# 1_P1.net
KiCad netlist of a schematic drawn in Altium Designer
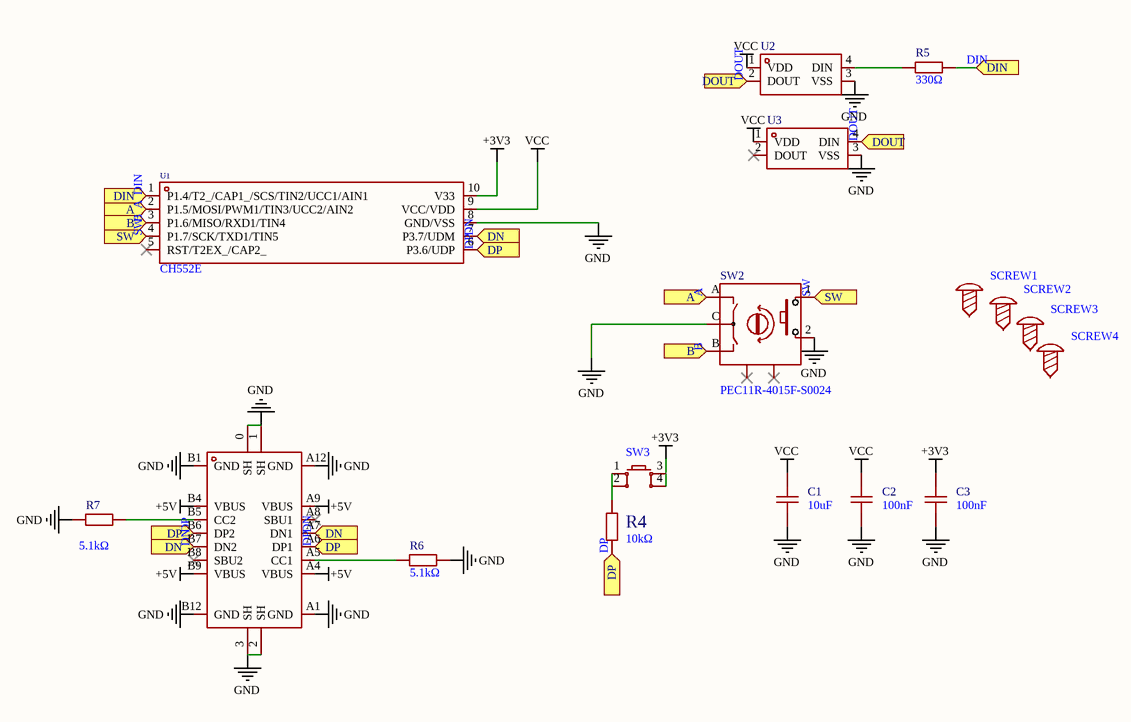
[diagram p0: 1_P1.schdoc]

(export (version "E")
  (design (tool "Eeschema 10.0.6"))
  (components
    (comp (ref "C1")
      (value "10uF")
      (footprint "C0603")
      (fields
        (field (name "MANUFACTURER") "SAMSUNG(三星)")
        (field (name "MANUFACTURER PART") "CL10A106KP8NNNC")
        (field (name "TOLERANCE") "±10%")
      )
      (libsource (lib "altium-import") (part "root_1_CL10A106KP8NNNC_"))
    )
    (comp (ref "C2")
      (value "100nF")
      (footprint "C0603")
      (fields
        (field (name "MANUFACTURER") "YAGEO(国巨)")
        (field (name "MANUFACTURER PART") "CC0603KRX7R9BB104")
        (field (name "TOLERANCE") "±10%")
      )
      (libsource (lib "altium-import") (part "root_1_CC0603KRX7R9BB104_"))
    )
    (comp (ref "C3")
      (value "100nF")
      (footprint "C0603")
      (fields
        (field (name "MANUFACTURER") "YAGEO(国巨)")
        (field (name "MANUFACTURER PART") "CC0603KRX7R9BB104")
        (field (name "TOLERANCE") "±10%")
      )
      (libsource (lib "altium-import") (part "root_1_CC0603KRX7R9BB104_"))
    )
    (comp (ref "R4")
      (value "10kΩ")
      (footprint "R0603")
      (fields
        (field (name "MANUFACTURER") "UNI-ROYAL(厚声)")
        (field (name "MANUFACTURER PART") "0603WAF1002T5E")
        (field (name "TOLERANCE") "±1%")
      )
      (libsource (lib "altium-import") (part "root_1_0603WAF1002T5E_"))
    )
    (comp (ref "R5")
      (value "330Ω")
      (footprint "R0603")
      (fields
        (field (name "MANUFACTURER") "UNI-ROYAL(厚声)")
        (field (name "MANUFACTURER PART") "0603WAF3300T5E")
        (field (name "TOLERANCE") "±1%")
      )
      (libsource (lib "altium-import") (part "root_0_0603WAF3300T5E_"))
    )
    (comp (ref "R6")
      (value "5.1kΩ")
      (footprint "R0603")
      (fields
        (field (name "MANUFACTURER") "UNI-ROYAL(厚声)")
        (field (name "MANUFACTURER PART") "0603WAF5101T5E")
        (field (name "TOLERANCE") "±1%")
      )
      (libsource (lib "altium-import") (part "root_0_0603WAF5101T5E_"))
    )
    (comp (ref "R7")
      (value "5.1kΩ")
      (footprint "R0603")
      (fields
        (field (name "MANUFACTURER") "UNI-ROYAL(厚声)")
        (field (name "MANUFACTURER PART") "0603WAF5101T5E")
        (field (name "TOLERANCE") "±1%")
      )
      (libsource (lib "altium-import") (part "root_0_0603WAF5101T5E_"))
    )
    (comp (ref "SCREW1")
      (value "~")
      (footprint "Screw-Hole-M2")
      (libsource (lib "altium-import") (part "root_0_Screw-Hole-M2_"))
    )
    (comp (ref "SCREW2")
      (value "~")
      (footprint "Screw-Hole-M2")
      (libsource (lib "altium-import") (part "root_0_Screw-Hole-M2_"))
    )
    (comp (ref "SCREW3")
      (value "~")
      (footprint "Screw-Hole-M2")
      (libsource (lib "altium-import") (part "root_0_Screw-Hole-M2_"))
    )
    (comp (ref "SCREW4")
      (value "~")
      (footprint "Screw-Hole-M2")
      (libsource (lib "altium-import") (part "root_0_Screw-Hole-M2_"))
    )
    (comp (ref "SW2")
      (value "PEC11R-4015F-S0024")
      (footprint "SW-TH_PEC11R-4XXXF-SXXXX")
      (fields (field (name "MANUFACTURER") "BOURNS"))
      (libsource (lib "altium-import") (part "root_0_PEC11R-4015F-S0024_"))
    )
    (comp (ref "SW3")
      (value "~")
      (footprint "KEY-TH_4P-L6.0-W6.0-P3.90-LS6.5")
      (libsource (lib "altium-import") (part "root_0_Key_TH_6x6x4.5_"))
    )
    (comp (ref "U1")
      (value "CH552E")
      (footprint "MSOP-10_L3.0-W3.0-P0.50-LS5.0-BL")
      (fields (field (name "MANUFACTURER") "WCH(南京沁恒)"))
      (libsource (lib "altium-import") (part "root_0_CH552E_"))
    )
    (comp (ref "U2")
      (value "WS2812B-HS01/W")
      (footprint "LED-SMD_4P-L5.0-W5.0-TL-1")
      (fields (field (name "MANUFACTURER") "worldsemi"))
      (libsource (lib "altium-import") (part "root_0_WS2812B-HS01/W_"))
    )
    (comp (ref "U3")
      (value "WS2812B-HS01/W")
      (footprint "LED-SMD_4P-L5.0-W5.0-TL-1")
      (fields (field (name "MANUFACTURER") "worldsemi"))
      (libsource (lib "altium-import") (part "root_0_WS2812B-HS01/W_"))
    )
    (comp (ref "USBC2")
      (value "TYPE-C-31-M-12")
      (footprint "USB-C_SMD-TYPE-C-31-M-12")
      (fields (field (name "MANUFACTURER") "韩国韩荣"))
      (libsource (lib "altium-import") (part "root_0_TYPE-C-31-M-12_"))
    )
  )
  (nets
    (net (code "1") (name "+3V3") (class "Default")
      (node (ref "C3") (pin "2") (pinfunction "2_2") (pintype "passive"))
      (node (ref "U1") (pin "10") (pinfunction "V33_10") (pintype "passive"))
    )
    (net (code "2") (name "+5V") (class "Default")
      (node (ref "USBC2") (pin "A4") (pinfunction "VBUS_A4") (pintype "passive"))
      (node (ref "USBC2") (pin "A9") (pinfunction "VBUS_A9") (pintype "passive"))
      (node (ref "USBC2") (pin "B4") (pinfunction "VBUS_B4") (pintype "passive"))
      (node (ref "USBC2") (pin "B9") (pinfunction "VBUS_B9") (pintype "passive"))
    )
    (net (code "3") (name "/A") (class "Default")
      (node (ref "SW2") (pin "A") (pinfunction "A_A") (pintype "passive"))
      (node (ref "U1") (pin "2") (pinfunction "P1.5/MOSI/PWM1/TIN3/UCC2/AIN2_2") (pintype "passive"))
    )
    (net (code "4") (name "/B") (class "Default")
      (node (ref "SW2") (pin "B") (pinfunction "B_B") (pintype "passive"))
      (node (ref "U1") (pin "3") (pinfunction "P1.6/MISO/RXD1/TIN4_3") (pintype "passive"))
    )
    (net (code "5") (name "/DIN") (class "Default")
      (node (ref "R5") (pin "2") (pinfunction "2_2") (pintype "passive"))
      (node (ref "U1") (pin "1") (pinfunction "P1.4/T2_/CAP1_/SCS/TIN2/UCC1/AIN1_1") (pintype "passive"))
    )
    (net (code "6") (name "/DN") (class "Default")
      (node (ref "U1") (pin "7") (pinfunction "P3.7/UDM_7") (pintype "passive"))
      (node (ref "USBC2") (pin "A7") (pinfunction "DN1_A7") (pintype "passive"))
      (node (ref "USBC2") (pin "B7") (pinfunction "DN2_B7") (pintype "passive"))
    )
    (net (code "7") (name "/DOUT") (class "Default")
      (node (ref "U2") (pin "2") (pinfunction "DOUT_2") (pintype "passive"))
      (node (ref "U3") (pin "4") (pinfunction "DIN_4") (pintype "passive"))
    )
    (net (code "8") (name "/DP") (class "Default")
      (node (ref "R4") (pin "1") (pinfunction "1_1") (pintype "passive"))
      (node (ref "U1") (pin "6") (pinfunction "P3.6/UDP_6") (pintype "passive"))
      (node (ref "USBC2") (pin "A6") (pinfunction "DP1_A6") (pintype "passive"))
      (node (ref "USBC2") (pin "B6") (pinfunction "DP2_B6") (pintype "passive"))
    )
    (net (code "9") (name "/SW") (class "Default")
      (node (ref "SW2") (pin "1") (pinfunction "1_1") (pintype "passive"))
      (node (ref "U1") (pin "4") (pinfunction "P1.7/SCK/TXD1/TIN5_4") (pintype "passive"))
    )
    (net (code "10") (name "GND") (class "Default")
      (node (ref "C1") (pin "1") (pinfunction "1_1") (pintype "passive"))
      (node (ref "C2") (pin "1") (pinfunction "1_1") (pintype "passive"))
      (node (ref "C3") (pin "1") (pinfunction "1_1") (pintype "passive"))
      (node (ref "R6") (pin "2") (pinfunction "2_2") (pintype "passive"))
      (node (ref "R7") (pin "1") (pinfunction "1_1") (pintype "passive"))
      (node (ref "SW2") (pin "2") (pinfunction "2_2") (pintype "passive"))
      (node (ref "SW2") (pin "C") (pinfunction "C_C") (pintype "passive"))
      (node (ref "U1") (pin "8") (pinfunction "GND/VSS_8") (pintype "passive"))
      (node (ref "U2") (pin "3") (pinfunction "VSS_3") (pintype "passive"))
      (node (ref "U3") (pin "3") (pinfunction "VSS_3") (pintype "passive"))
      (node (ref "USBC2") (pin "0") (pinfunction "SH_0") (pintype "passive"))
      (node (ref "USBC2") (pin "1") (pinfunction "SH_1") (pintype "passive"))
      (node (ref "USBC2") (pin "2") (pinfunction "SH_2") (pintype "passive"))
      (node (ref "USBC2") (pin "3") (pinfunction "SH_3") (pintype "passive"))
      (node (ref "USBC2") (pin "A1") (pinfunction "GND_A1") (pintype "passive"))
      (node (ref "USBC2") (pin "A12") (pinfunction "GND_A12") (pintype "passive"))
      (node (ref "USBC2") (pin "B1") (pinfunction "GND_B1") (pintype "passive"))
      (node (ref "USBC2") (pin "B12") (pinfunction "GND_B12") (pintype "passive"))
    )
    (net (code "11") (name "Net-(R4-Pad2)") (class "Default")
      (node (ref "R4") (pin "2") (pinfunction "2_2") (pintype "passive"))
      (node (ref "SW3") (pin "1") (pinfunction "1_1") (pintype "passive"))
      (node (ref "SW3") (pin "2") (pinfunction "2_2") (pintype "passive"))
    )
    (net (code "12") (name "Net-(SW3-Pad3)") (class "Default")
      (node (ref "SW3") (pin "3") (pinfunction "3_3") (pintype "passive"))
      (node (ref "SW3") (pin "4") (pinfunction "4_4") (pintype "passive"))
    )
    (net (code "13") (name "Net-(U2-DIN)") (class "Default")
      (node (ref "R5") (pin "1") (pinfunction "1_1") (pintype "passive"))
      (node (ref "U2") (pin "4") (pinfunction "DIN_4") (pintype "passive"))
    )
    (net (code "14") (name "Net-(USBC2-CC1)") (class "Default")
      (node (ref "R6") (pin "1") (pinfunction "1_1") (pintype "passive"))
      (node (ref "USBC2") (pin "A5") (pinfunction "CC1_A5") (pintype "passive"))
    )
    (net (code "15") (name "Net-(USBC2-CC2)") (class "Default")
      (node (ref "R7") (pin "2") (pinfunction "2_2") (pintype "passive"))
      (node (ref "USBC2") (pin "B5") (pinfunction "CC2_B5") (pintype "passive"))
    )
    (net (code "16") (name "VCC") (class "Default")
      (node (ref "C1") (pin "2") (pinfunction "2_2") (pintype "passive"))
      (node (ref "C2") (pin "2") (pinfunction "2_2") (pintype "passive"))
      (node (ref "U1") (pin "9") (pinfunction "VCC/VDD_9") (pintype "passive"))
      (node (ref "U2") (pin "1") (pinfunction "VDD_1") (pintype "passive"))
      (node (ref "U3") (pin "1") (pinfunction "VDD_1") (pintype "passive"))
    )
    (net (code "17") (name "unconnected-(SCREW1-Pad1)") (class "Default")
      (node (ref "SCREW1") (pin "1") (pinfunction "1_1") (pintype "passive"))
    )
    (net (code "18") (name "unconnected-(SCREW2-Pad1)") (class "Default")
      (node (ref "SCREW2") (pin "1") (pinfunction "1_1") (pintype "passive"))
    )
    (net (code "19") (name "unconnected-(SCREW3-Pad1)") (class "Default")
      (node (ref "SCREW3") (pin "1") (pinfunction "1_1") (pintype "passive"))
    )
    (net (code "20") (name "unconnected-(SCREW4-Pad1)") (class "Default")
      (node (ref "SCREW4") (pin "1") (pinfunction "1_1") (pintype "passive"))
    )
    (net (code "21") (name "unconnected-(SW2-PadMT1)") (class "Default")
      (node (ref "SW2") (pin "MT1") (pinfunction "MT1_MT1") (pintype "passive+no_connect"))
    )
    (net (code "22") (name "unconnected-(SW2-PadMT2)") (class "Default")
      (node (ref "SW2") (pin "MT2") (pinfunction "MT2_MT2") (pintype "passive+no_connect"))
    )
    (net (code "23") (name "unconnected-(U1-RST{slash}T2EX_{slash}CAP2_-Pad5)") (class "Default")
      (node (ref "U1") (pin "5") (pinfunction "RST/T2EX_/CAP2__5") (pintype "passive+no_connect"))
    )
    (net (code "24") (name "unconnected-(U3-DOUT-Pad2)") (class "Default")
      (node (ref "U3") (pin "2") (pinfunction "DOUT_2") (pintype "passive+no_connect"))
    )
    (net (code "25") (name "unconnected-(USBC2-SBU1-PadA8)") (class "Default")
      (node (ref "USBC2") (pin "A8") (pinfunction "SBU1_A8") (pintype "passive+no_connect"))
    )
    (net (code "26") (name "unconnected-(USBC2-SBU2-PadB8)") (class "Default")
      (node (ref "USBC2") (pin "B8") (pinfunction "SBU2_B8") (pintype "passive+no_connect"))
    )
  )
)
